# RP2040.net
KiCad netlist of a schematic drawn in Altium Designer
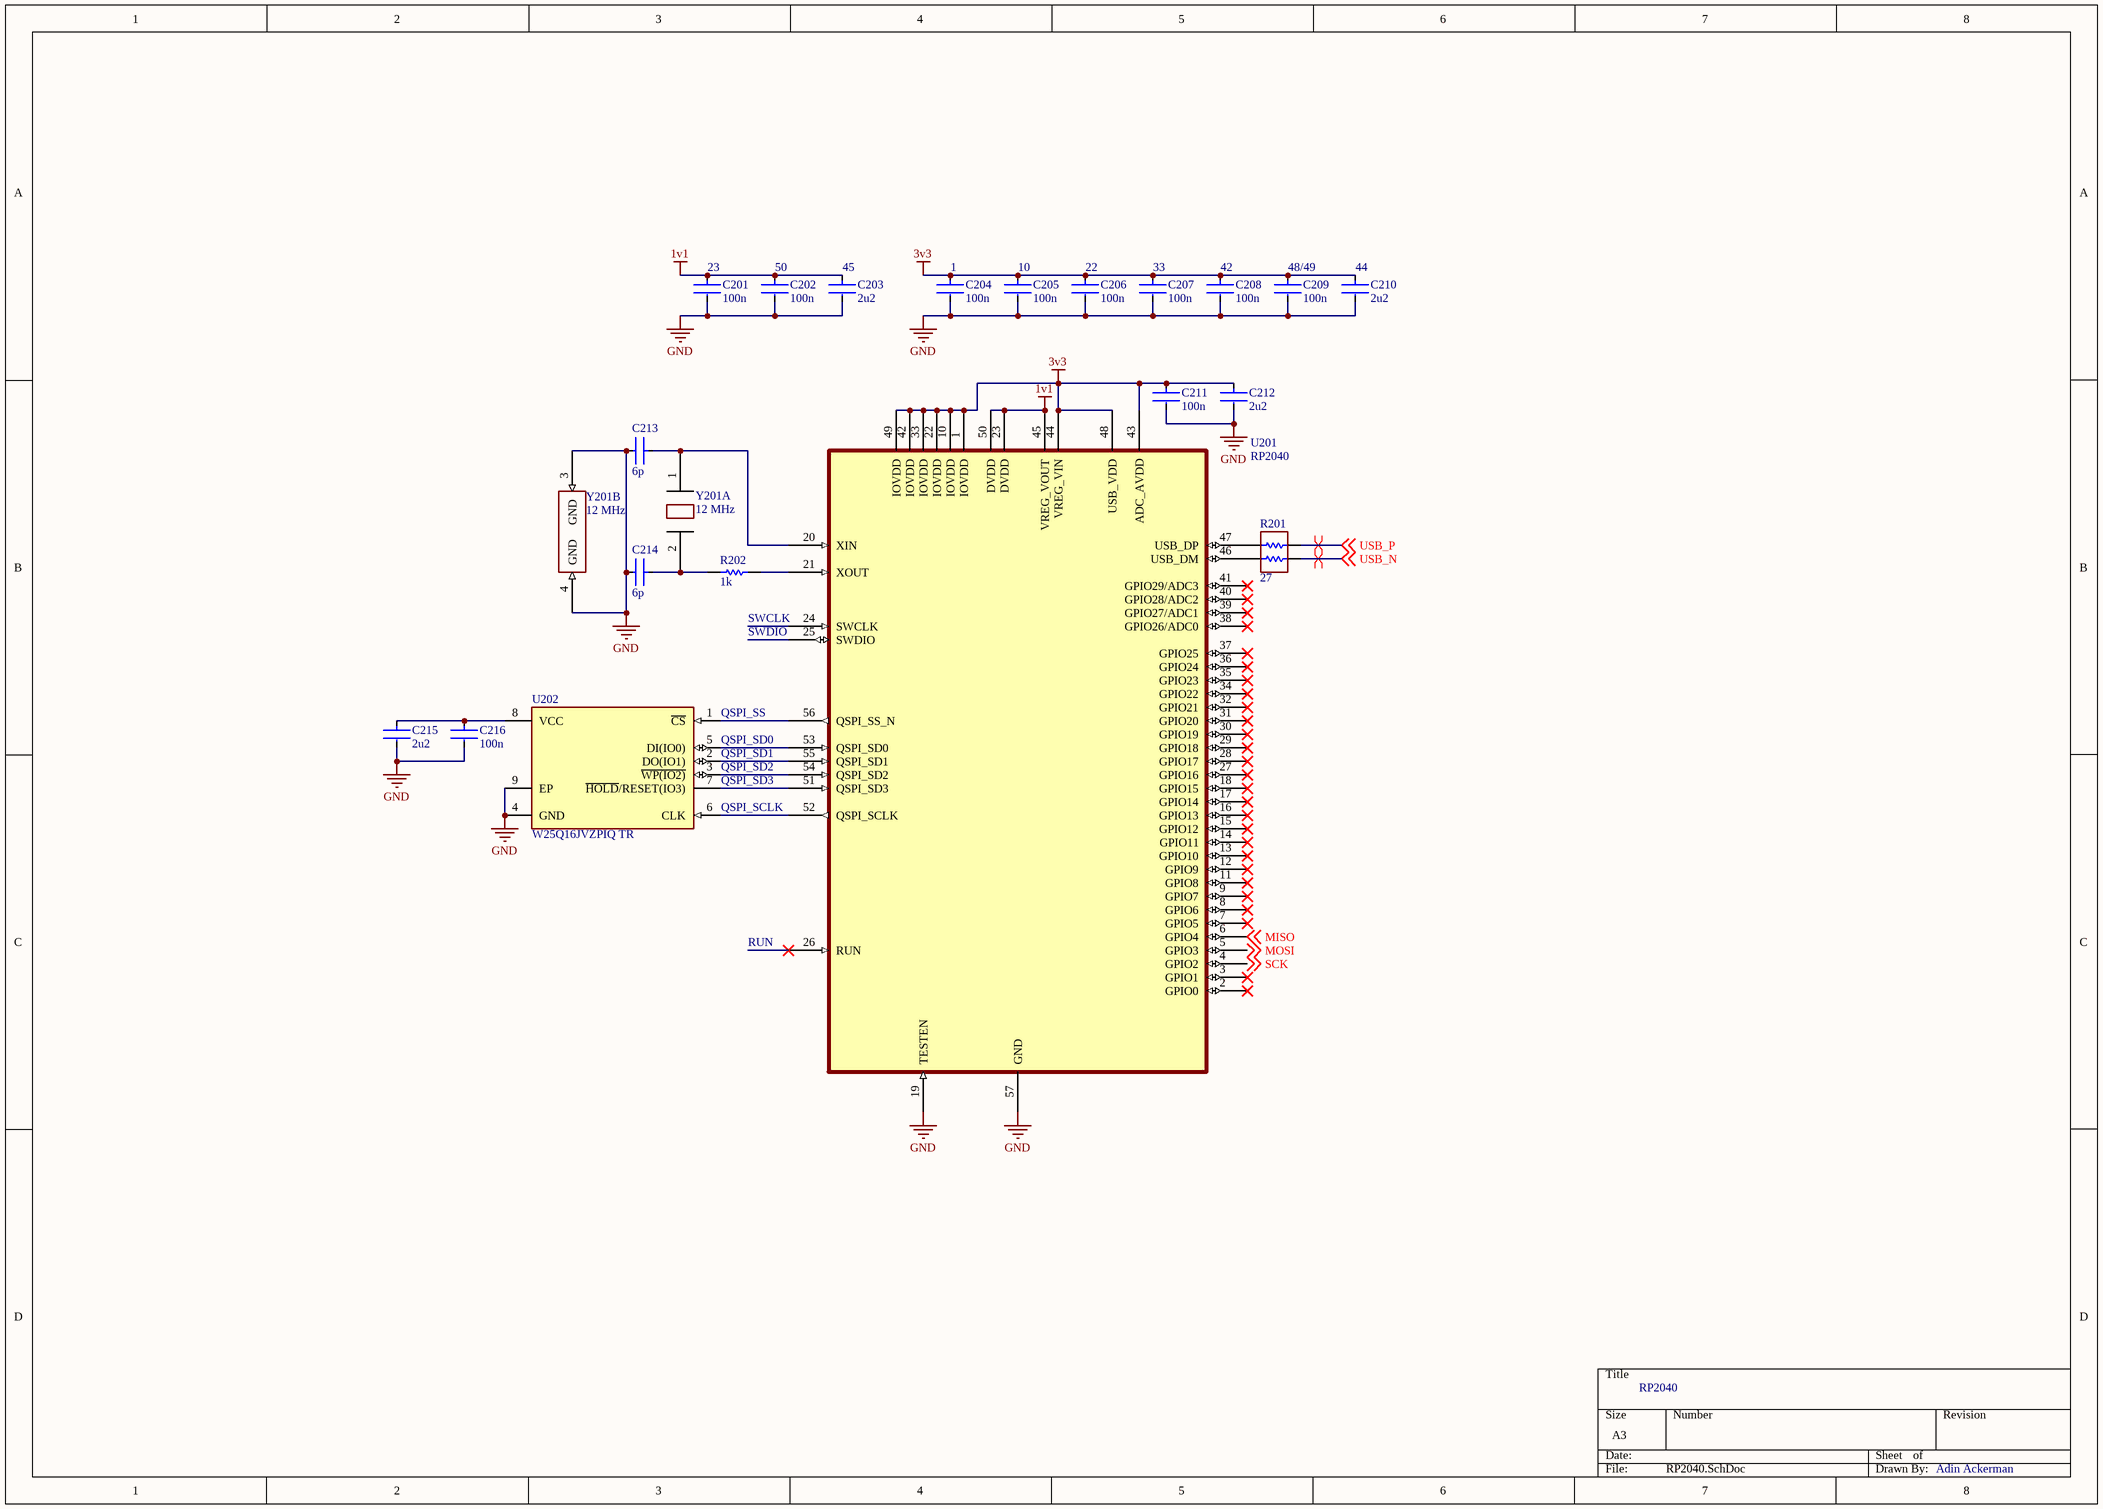
[diagram p0: RP2040.SchDoc]

(export (version "E")
  (design (tool "Eeschema 10.0.6"))
  (components
    (comp (ref "C201")
      (value "100n")
      (footprint "FP-GCM155-0_05-MFG")
      (description "Ceramic Capacitor for Automotive 100nF ±10% 50VDC X7R 0402 Paper T/R")
      (fields (field (name "TOLERANCE") "10%"))
      (libsource (lib "Main") (part "GCM155R71H104KE02J"))
    )
    (comp (ref "C202")
      (value "100n")
      (footprint "FP-GCM155-0_05-MFG")
      (description "Ceramic Capacitor for Automotive 100nF ±10% 50VDC X7R 0402 Paper T/R")
      (fields (field (name "TOLERANCE") "10%"))
      (libsource (lib "Main") (part "GCM155R71H104KE02J"))
    )
    (comp (ref "C203")
      (value "2u2")
      (footprint "CAPC1608X10N")
      (description "Multilayer Ceramic Capacitors MLCC - SMD/SMT 0603 50Vdc 2.2uF X5R 20%")
      (libsource (lib "Main") (part "GRT188R61H225ME13D"))
    )
    (comp (ref "C204")
      (value "100n")
      (footprint "FP-GCM155-0_05-MFG")
      (description "Ceramic Capacitor for Automotive 100nF ±10% 50VDC X7R 0402 Paper T/R")
      (fields (field (name "TOLERANCE") "10%"))
      (libsource (lib "Main") (part "GCM155R71H104KE02J"))
    )
    (comp (ref "C205")
      (value "100n")
      (footprint "FP-GCM155-0_05-MFG")
      (description "Ceramic Capacitor for Automotive 100nF ±10% 50VDC X7R 0402 Paper T/R")
      (fields (field (name "TOLERANCE") "10%"))
      (libsource (lib "Main") (part "GCM155R71H104KE02J"))
    )
    (comp (ref "C206")
      (value "100n")
      (footprint "FP-GCM155-0_05-MFG")
      (description "Ceramic Capacitor for Automotive 100nF ±10% 50VDC X7R 0402 Paper T/R")
      (fields (field (name "TOLERANCE") "10%"))
      (libsource (lib "Main") (part "GCM155R71H104KE02J"))
    )
    (comp (ref "C207")
      (value "100n")
      (footprint "FP-GCM155-0_05-MFG")
      (description "Ceramic Capacitor for Automotive 100nF ±10% 50VDC X7R 0402 Paper T/R")
      (fields (field (name "TOLERANCE") "10%"))
      (libsource (lib "Main") (part "GCM155R71H104KE02J"))
    )
    (comp (ref "C208")
      (value "100n")
      (footprint "FP-GCM155-0_05-MFG")
      (description "Ceramic Capacitor for Automotive 100nF ±10% 50VDC X7R 0402 Paper T/R")
      (fields (field (name "TOLERANCE") "10%"))
      (libsource (lib "Main") (part "GCM155R71H104KE02J"))
    )
    (comp (ref "C209")
      (value "100n")
      (footprint "FP-GCM155-0_05-MFG")
      (description "Ceramic Capacitor for Automotive 100nF ±10% 50VDC X7R 0402 Paper T/R")
      (fields (field (name "TOLERANCE") "10%"))
      (libsource (lib "Main") (part "GCM155R71H104KE02J"))
    )
    (comp (ref "C210")
      (value "2u2")
      (footprint "CAPC1608X10N")
      (description "Multilayer Ceramic Capacitors MLCC - SMD/SMT 0603 50Vdc 2.2uF X5R 20%")
      (libsource (lib "Main") (part "GRT188R61H225ME13D"))
    )
    (comp (ref "C211")
      (value "100n")
      (footprint "FP-GCM155-0_05-MFG")
      (description "Ceramic Capacitor for Automotive 100nF ±10% 50VDC X7R 0402 Paper T/R")
      (fields (field (name "TOLERANCE") "10%"))
      (libsource (lib "Main") (part "GCM155R71H104KE02J"))
    )
    (comp (ref "C212")
      (value "2u2")
      (footprint "CAPC1608X10N")
      (description "Multilayer Ceramic Capacitors MLCC - SMD/SMT 0603 50Vdc 2.2uF X5R 20%")
      (libsource (lib "Main") (part "GRT188R61H225ME13D"))
    )
    (comp (ref "C213")
      (value "6p")
      (footprint "FP-GCQ155-0_05-MFG")
      (description "High Q Ceramic Capacitor for Automotive 6pF ±0.1pF 50VDC C0G 0402 Paper T/R")
      (libsource (lib "Main") (part "GCQ1555C1H6R0BB01D"))
    )
    (comp (ref "C214")
      (value "6p")
      (footprint "FP-GCQ155-0_05-MFG")
      (description "High Q Ceramic Capacitor for Automotive 6pF ±0.1pF 50VDC C0G 0402 Paper T/R")
      (libsource (lib "Main") (part "GCQ1555C1H6R0BB01D"))
    )
    (comp (ref "C215")
      (value "2u2")
      (footprint "CAPC1608X10N")
      (description "Multilayer Ceramic Capacitors MLCC - SMD/SMT 0603 50Vdc 2.2uF X5R 20%")
      (libsource (lib "Main") (part "GRT188R61H225ME13D"))
    )
    (comp (ref "C216")
      (value "100n")
      (footprint "FP-GCM155-0_05-MFG")
      (description "Ceramic Capacitor for Automotive 100nF ±10% 50VDC X7R 0402 Paper T/R")
      (fields (field (name "TOLERANCE") "10%"))
      (libsource (lib "Main") (part "GCM155R71H104KE02J"))
    )
    (comp (ref "R201")
      (value "27")
      (footprint "CAC-65P100X100-4L")
      (libsource (lib "Main") (part "EXB-24V270JX"))
    )
    (comp (ref "R202")
      (value "1k")
      (footprint "RESC1005X04N")
      (fields (field (name "MANUFACTURER") "Panasonic") (field (name "PART NUMBER") "ERJ-2GEJ102X"))
      (libsource (lib "Main") (part "ERJ-2GEJ102X"))
    )
    (comp (ref "U201")
      (value "RP2040")
      (footprint "QFN40P700X700X90_HS-57N")
      (libsource (lib "Main") (part "RP2040"))
    )
    (comp (ref "U202")
      (value "W25Q16JVZPIQ TR")
      (footprint "WSON-8")
      (description "IC FLASH 16M SPI 133MHZ 8WSON")
      (libsource (lib "Main") (part "W25Q16JVZPIQ TR"))
    )
    (comp (ref "Y201") (value "12 MHz") (libsource (lib "Main") (part "ABM10-166-12.000MHZ-T3")))
  )
  (nets
    (net (code "1") (name "1v1") (class "Default")
      (node (ref "C201") (pin "1") (pinfunction "1_1") (pintype "passive"))
      (node (ref "C202") (pin "1") (pinfunction "1_1") (pintype "passive"))
      (node (ref "C203") (pin "1") (pinfunction "1_1") (pintype "passive"))
      (node (ref "U201") (pin "23") (pinfunction "DVDD_23") (pintype "power_in"))
      (node (ref "U201") (pin "45") (pinfunction "VREG_VOUT_45") (pintype "power_in"))
      (node (ref "U201") (pin "50") (pinfunction "DVDD_50") (pintype "power_in"))
    )
    (net (code "2") (name "3v3") (class "Default")
      (node (ref "C204") (pin "1") (pinfunction "1_1") (pintype "passive"))
      (node (ref "C205") (pin "1") (pinfunction "1_1") (pintype "passive"))
      (node (ref "C206") (pin "1") (pinfunction "1_1") (pintype "passive"))
      (node (ref "C207") (pin "1") (pinfunction "1_1") (pintype "passive"))
      (node (ref "C208") (pin "1") (pinfunction "1_1") (pintype "passive"))
      (node (ref "C209") (pin "1") (pinfunction "1_1") (pintype "passive"))
      (node (ref "C210") (pin "1") (pinfunction "1_1") (pintype "passive"))
      (node (ref "C211") (pin "1") (pinfunction "1_1") (pintype "passive"))
      (node (ref "C212") (pin "1") (pinfunction "1_1") (pintype "passive"))
      (node (ref "U201") (pin "1") (pinfunction "IOVDD_1") (pintype "power_in"))
      (node (ref "U201") (pin "10") (pinfunction "IOVDD_10") (pintype "power_in"))
      (node (ref "U201") (pin "22") (pinfunction "IOVDD_22") (pintype "power_in"))
      (node (ref "U201") (pin "33") (pinfunction "IOVDD_33") (pintype "power_in"))
      (node (ref "U201") (pin "42") (pinfunction "IOVDD_42") (pintype "power_in"))
      (node (ref "U201") (pin "43") (pinfunction "ADC_AVDD_43") (pintype "power_in"))
      (node (ref "U201") (pin "44") (pinfunction "VREG_VIN_44") (pintype "power_in"))
      (node (ref "U201") (pin "48") (pinfunction "USB_VDD_48") (pintype "power_in"))
      (node (ref "U201") (pin "49") (pinfunction "IOVDD_49") (pintype "power_in"))
    )
    (net (code "3") (name "GND") (class "Default")
      (node (ref "C201") (pin "2") (pinfunction "2_2") (pintype "passive"))
      (node (ref "C202") (pin "2") (pinfunction "2_2") (pintype "passive"))
      (node (ref "C203") (pin "2") (pinfunction "2_2") (pintype "passive"))
      (node (ref "C204") (pin "2") (pinfunction "2_2") (pintype "passive"))
      (node (ref "C205") (pin "2") (pinfunction "2_2") (pintype "passive"))
      (node (ref "C206") (pin "2") (pinfunction "2_2") (pintype "passive"))
      (node (ref "C207") (pin "2") (pinfunction "2_2") (pintype "passive"))
      (node (ref "C208") (pin "2") (pinfunction "2_2") (pintype "passive"))
      (node (ref "C209") (pin "2") (pinfunction "2_2") (pintype "passive"))
      (node (ref "C210") (pin "2") (pinfunction "2_2") (pintype "passive"))
      (node (ref "C211") (pin "2") (pinfunction "2_2") (pintype "passive"))
      (node (ref "C212") (pin "2") (pinfunction "2_2") (pintype "passive"))
      (node (ref "C213") (pin "2") (pinfunction "2_2") (pintype "passive"))
      (node (ref "C214") (pin "2") (pinfunction "2_2") (pintype "passive"))
      (node (ref "C215") (pin "2") (pinfunction "2_2") (pintype "passive"))
      (node (ref "C216") (pin "2") (pinfunction "2_2") (pintype "passive"))
      (node (ref "U201") (pin "19") (pinfunction "TESTEN_19") (pintype "input"))
      (node (ref "U201") (pin "57") (pinfunction "GND_57") (pintype "power_in"))
      (node (ref "U202") (pin "4") (pinfunction "GND_4") (pintype "power_in"))
      (node (ref "U202") (pin "9") (pinfunction "EP_9") (pintype "passive"))
      (node (ref "Y201") (pin "3") (pinfunction "GND_3") (pintype "input"))
      (node (ref "Y201") (pin "4") (pinfunction "GND_4") (pintype "input"))
    )
    (net (code "4") (name "MISO") (class "Default")
      (node (ref "U201") (pin "6") (pinfunction "GPIO4_6") (pintype "bidirectional"))
    )
    (net (code "5") (name "MOSI") (class "Default")
      (node (ref "U201") (pin "5") (pinfunction "GPIO3_5") (pintype "bidirectional"))
    )
    (net (code "6") (name "Net-(C214-Pad1)") (class "Default")
      (node (ref "C214") (pin "1") (pinfunction "1_1") (pintype "passive"))
      (node (ref "R202") (pin "1") (pinfunction "1_1") (pintype "passive"))
      (node (ref "Y201") (pin "2") (pintype "passive"))
    )
    (net (code "7") (name "Net-(U201-QSPI_SCLK)") (class "Default")
      (node (ref "U201") (pin "52") (pinfunction "QSPI_SCLK_52") (pintype "output"))
      (node (ref "U202") (pin "6") (pinfunction "CLK_6") (pintype "input"))
    )
    (net (code "8") (name "Net-(U201-QSPI_SD0)") (class "Default")
      (node (ref "U201") (pin "53") (pinfunction "QSPI_SD0_53") (pintype "input"))
      (node (ref "U202") (pin "5") (pinfunction "DI(IO0)_5") (pintype "bidirectional"))
    )
    (net (code "9") (name "Net-(U201-QSPI_SD1)") (class "Default")
      (node (ref "U201") (pin "55") (pinfunction "QSPI_SD1_55") (pintype "input"))
      (node (ref "U202") (pin "2") (pinfunction "DO(IO1)_2") (pintype "bidirectional"))
    )
    (net (code "10") (name "Net-(U201-QSPI_SD2)") (class "Default")
      (node (ref "U201") (pin "54") (pinfunction "QSPI_SD2_54") (pintype "input"))
      (node (ref "U202") (pin "3") (pinfunction "~{WP(IO2)}_3") (pintype "bidirectional"))
    )
    (net (code "11") (name "Net-(U201-QSPI_SD3)") (class "Default")
      (node (ref "U201") (pin "51") (pinfunction "QSPI_SD3_51") (pintype "input"))
      (node (ref "U202") (pin "7") (pinfunction "~{HOLD}/RESET(IO3)_7") (pintype "passive"))
    )
    (net (code "12") (name "Net-(U201-QSPI_SS_N)") (class "Default")
      (node (ref "U201") (pin "56") (pinfunction "QSPI_SS_N_56") (pintype "output"))
      (node (ref "U202") (pin "1") (pinfunction "~{CS}_1") (pintype "input"))
    )
    (net (code "13") (name "Net-(U201-USB_DM)") (class "Default")
      (node (ref "R201") (pin "2") (pinfunction "2_2") (pintype "passive"))
      (node (ref "U201") (pin "46") (pinfunction "USB_DM_46") (pintype "bidirectional"))
    )
    (net (code "14") (name "Net-(U201-USB_DP)") (class "Default")
      (node (ref "R201") (pin "1") (pinfunction "1_1") (pintype "passive"))
      (node (ref "U201") (pin "47") (pinfunction "USB_DP_47") (pintype "bidirectional"))
    )
    (net (code "15") (name "Net-(U201-XIN)") (class "Default")
      (node (ref "C213") (pin "1") (pinfunction "1_1") (pintype "passive"))
      (node (ref "U201") (pin "20") (pinfunction "XIN_20") (pintype "input"))
      (node (ref "Y201") (pin "1") (pintype "passive"))
    )
    (net (code "16") (name "Net-(U201-XOUT)") (class "Default")
      (node (ref "R202") (pin "2") (pinfunction "2_2") (pintype "passive"))
      (node (ref "U201") (pin "21") (pinfunction "XOUT_21") (pintype "input"))
    )
    (net (code "17") (name "Net-(U202-VCC)") (class "Default")
      (node (ref "C215") (pin "1") (pinfunction "1_1") (pintype "passive"))
      (node (ref "C216") (pin "1") (pinfunction "1_1") (pintype "passive"))
      (node (ref "U202") (pin "8") (pinfunction "VCC_8") (pintype "power_in"))
    )
    (net (code "18") (name "SCK") (class "Default")
      (node (ref "U201") (pin "4") (pinfunction "GPIO2_4") (pintype "bidirectional"))
    )
    (net (code "19") (name "USB_N") (class "Default")
      (node (ref "R201") (pin "3") (pinfunction "3_3") (pintype "passive"))
    )
    (net (code "20") (name "USB_P") (class "Default")
      (node (ref "R201") (pin "4") (pinfunction "4_4") (pintype "passive"))
    )
    (net (code "21") (name "unconnected-(U201-GPIO0-Pad2)") (class "Default")
      (node (ref "U201") (pin "2") (pinfunction "GPIO0_2") (pintype "bidirectional+no_connect"))
    )
    (net (code "22") (name "unconnected-(U201-GPIO1-Pad3)") (class "Default")
      (node (ref "U201") (pin "3") (pinfunction "GPIO1_3") (pintype "bidirectional+no_connect"))
    )
    (net (code "23") (name "unconnected-(U201-GPIO5-Pad7)") (class "Default")
      (node (ref "U201") (pin "7") (pinfunction "GPIO5_7") (pintype "bidirectional+no_connect"))
    )
    (net (code "24") (name "unconnected-(U201-GPIO6-Pad8)") (class "Default")
      (node (ref "U201") (pin "8") (pinfunction "GPIO6_8") (pintype "bidirectional+no_connect"))
    )
    (net (code "25") (name "unconnected-(U201-GPIO7-Pad9)") (class "Default")
      (node (ref "U201") (pin "9") (pinfunction "GPIO7_9") (pintype "bidirectional+no_connect"))
    )
    (net (code "26") (name "unconnected-(U201-GPIO8-Pad11)") (class "Default")
      (node (ref "U201") (pin "11") (pinfunction "GPIO8_11") (pintype "bidirectional+no_connect"))
    )
    (net (code "27") (name "unconnected-(U201-GPIO9-Pad12)") (class "Default")
      (node (ref "U201") (pin "12") (pinfunction "GPIO9_12") (pintype "bidirectional+no_connect"))
    )
    (net (code "28") (name "unconnected-(U201-GPIO10-Pad13)") (class "Default")
      (node (ref "U201") (pin "13") (pinfunction "GPIO10_13") (pintype "bidirectional+no_connect"))
    )
    (net (code "29") (name "unconnected-(U201-GPIO11-Pad14)") (class "Default")
      (node (ref "U201") (pin "14") (pinfunction "GPIO11_14") (pintype "bidirectional+no_connect"))
    )
    (net (code "30") (name "unconnected-(U201-GPIO12-Pad15)") (class "Default")
      (node (ref "U201") (pin "15") (pinfunction "GPIO12_15") (pintype "bidirectional+no_connect"))
    )
    (net (code "31") (name "unconnected-(U201-GPIO13-Pad16)") (class "Default")
      (node (ref "U201") (pin "16") (pinfunction "GPIO13_16") (pintype "bidirectional+no_connect"))
    )
    (net (code "32") (name "unconnected-(U201-GPIO14-Pad17)") (class "Default")
      (node (ref "U201") (pin "17") (pinfunction "GPIO14_17") (pintype "bidirectional+no_connect"))
    )
    (net (code "33") (name "unconnected-(U201-GPIO15-Pad18)") (class "Default")
      (node (ref "U201") (pin "18") (pinfunction "GPIO15_18") (pintype "bidirectional+no_connect"))
    )
    (net (code "34") (name "unconnected-(U201-GPIO16-Pad27)") (class "Default")
      (node (ref "U201") (pin "27") (pinfunction "GPIO16_27") (pintype "bidirectional+no_connect"))
    )
    (net (code "35") (name "unconnected-(U201-GPIO17-Pad28)") (class "Default")
      (node (ref "U201") (pin "28") (pinfunction "GPIO17_28") (pintype "bidirectional+no_connect"))
    )
    (net (code "36") (name "unconnected-(U201-GPIO18-Pad29)") (class "Default")
      (node (ref "U201") (pin "29") (pinfunction "GPIO18_29") (pintype "bidirectional+no_connect"))
    )
    (net (code "37") (name "unconnected-(U201-GPIO19-Pad30)") (class "Default")
      (node (ref "U201") (pin "30") (pinfunction "GPIO19_30") (pintype "bidirectional+no_connect"))
    )
    (net (code "38") (name "unconnected-(U201-GPIO20-Pad31)") (class "Default")
      (node (ref "U201") (pin "31") (pinfunction "GPIO20_31") (pintype "bidirectional+no_connect"))
    )
    (net (code "39") (name "unconnected-(U201-GPIO21-Pad32)") (class "Default")
      (node (ref "U201") (pin "32") (pinfunction "GPIO21_32") (pintype "bidirectional+no_connect"))
    )
    (net (code "40") (name "unconnected-(U201-GPIO22-Pad34)") (class "Default")
      (node (ref "U201") (pin "34") (pinfunction "GPIO22_34") (pintype "bidirectional+no_connect"))
    )
    (net (code "41") (name "unconnected-(U201-GPIO23-Pad35)") (class "Default")
      (node (ref "U201") (pin "35") (pinfunction "GPIO23_35") (pintype "bidirectional+no_connect"))
    )
    (net (code "42") (name "unconnected-(U201-GPIO24-Pad36)") (class "Default")
      (node (ref "U201") (pin "36") (pinfunction "GPIO24_36") (pintype "bidirectional+no_connect"))
    )
    (net (code "43") (name "unconnected-(U201-GPIO25-Pad37)") (class "Default")
      (node (ref "U201") (pin "37") (pinfunction "GPIO25_37") (pintype "bidirectional+no_connect"))
    )
    (net (code "44") (name "unconnected-(U201-GPIO26{slash}ADC0-Pad38)") (class "Default")
      (node (ref "U201") (pin "38") (pinfunction "GPIO26/ADC0_38") (pintype "bidirectional+no_connect"))
    )
    (net (code "45") (name "unconnected-(U201-GPIO27{slash}ADC1-Pad39)") (class "Default")
      (node (ref "U201") (pin "39") (pinfunction "GPIO27/ADC1_39") (pintype "bidirectional+no_connect"))
    )
    (net (code "46") (name "unconnected-(U201-GPIO28{slash}ADC2-Pad40)") (class "Default")
      (node (ref "U201") (pin "40") (pinfunction "GPIO28/ADC2_40") (pintype "bidirectional+no_connect"))
    )
    (net (code "47") (name "unconnected-(U201-GPIO29{slash}ADC3-Pad41)") (class "Default")
      (node (ref "U201") (pin "41") (pinfunction "GPIO29/ADC3_41") (pintype "bidirectional+no_connect"))
    )
    (net (code "48") (name "unconnected-(U201-RUN-Pad26)") (class "Default")
      (node (ref "U201") (pin "26") (pinfunction "RUN_26") (pintype "input+no_connect"))
    )
    (net (code "49") (name "unconnected-(U201-SWCLK-Pad24)") (class "Default")
      (node (ref "U201") (pin "24") (pinfunction "SWCLK_24") (pintype "input"))
    )
    (net (code "50") (name "unconnected-(U201-SWDIO-Pad25)") (class "Default")
      (node (ref "U201") (pin "25") (pinfunction "SWDIO_25") (pintype "bidirectional"))
    )
  )
)
